# PicoInterface.net
KiCad netlist of a schematic drawn in Altium Designer
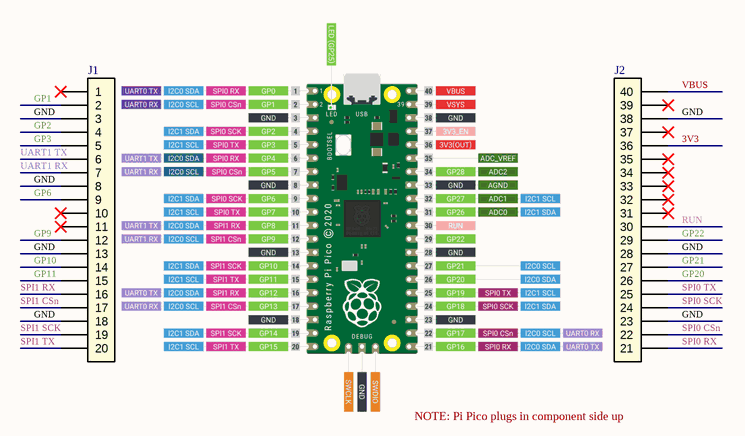
[diagram p0: PicoInterface.SchDoc]

(export (version "E")
  (design (tool "Eeschema 10.0.6"))
  (components
    (comp (ref "J1")
      (value "SSW-120-01-x-S")
      (footprint "SAMTEC_SSW-120-01-G-S")
      (description "Conn Socket Strip SKT 20 POS 2.54mm Solder ST Thru-Hole")
      (libsource (lib "Sainsbury Wellcome Centre") (part "Jack 20x1"))
    )
    (comp (ref "J2")
      (value "SSW-120-01-x-S - 21-40")
      (footprint "SAMTEC_SSW-120-01-G-S - 21-40")
      (description "Conn Socket Strip SKT 20 POS 2.54mm Solder ST Thru-Hole (pins 21 - 40)")
      (libsource (lib "Sainsbury Wellcome Centre") (part "Jack 20x1 21-40"))
    )
  )
  (nets
    (net (code "1") (name "/3V3") (class "Default")
      (node (ref "J2") (pin "36") (pinfunction "36_36") (pintype "passive"))
    )
    (net (code "2") (name "/GND") (class "Default")
      (node (ref "J1") (pin "13") (pinfunction "13_13") (pintype "passive"))
      (node (ref "J1") (pin "18") (pinfunction "18_18") (pintype "passive"))
      (node (ref "J1") (pin "3") (pinfunction "3_3") (pintype "passive"))
      (node (ref "J1") (pin "8") (pinfunction "8_8") (pintype "passive"))
      (node (ref "J2") (pin "23") (pinfunction "23_23") (pintype "passive"))
      (node (ref "J2") (pin "28") (pinfunction "28_28") (pintype "passive"))
      (node (ref "J2") (pin "38") (pinfunction "38_38") (pintype "passive"))
    )
    (net (code "3") (name "/GP1") (class "Default")
      (node (ref "J1") (pin "2") (pinfunction "2_2") (pintype "passive"))
    )
    (net (code "4") (name "/GP2") (class "Default")
      (node (ref "J1") (pin "4") (pinfunction "4_4") (pintype "passive"))
    )
    (net (code "5") (name "/GP3") (class "Default")
      (node (ref "J1") (pin "5") (pinfunction "5_5") (pintype "passive"))
    )
    (net (code "6") (name "/GP6") (class "Default")
      (node (ref "J1") (pin "9") (pinfunction "9_9") (pintype "passive"))
    )
    (net (code "7") (name "/GP9") (class "Default")
      (node (ref "J1") (pin "12") (pinfunction "12_12") (pintype "passive"))
    )
    (net (code "8") (name "/GP10") (class "Default")
      (node (ref "J1") (pin "14") (pinfunction "14_14") (pintype "passive"))
    )
    (net (code "9") (name "/GP11") (class "Default")
      (node (ref "J1") (pin "15") (pinfunction "15_15") (pintype "passive"))
    )
    (net (code "10") (name "/GP20") (class "Default")
      (node (ref "J2") (pin "26") (pinfunction "26_26") (pintype "passive"))
    )
    (net (code "11") (name "/GP21") (class "Default")
      (node (ref "J2") (pin "27") (pinfunction "27_27") (pintype "passive"))
    )
    (net (code "12") (name "/GP22") (class "Default")
      (node (ref "J2") (pin "29") (pinfunction "29_29") (pintype "passive"))
    )
    (net (code "13") (name "/RUN") (class "Default")
      (node (ref "J2") (pin "30") (pinfunction "30_30") (pintype "passive"))
    )
    (net (code "14") (name "/SPI0 CSn") (class "Default")
      (node (ref "J2") (pin "22") (pinfunction "22_22") (pintype "passive"))
    )
    (net (code "15") (name "/SPI0 RX") (class "Default")
      (node (ref "J2") (pin "21") (pinfunction "21_21") (pintype "passive"))
    )
    (net (code "16") (name "/SPI0 SCK") (class "Default")
      (node (ref "J2") (pin "24") (pinfunction "24_24") (pintype "passive"))
    )
    (net (code "17") (name "/SPI0 TX") (class "Default")
      (node (ref "J2") (pin "25") (pinfunction "25_25") (pintype "passive"))
    )
    (net (code "18") (name "/SPI1 CSn") (class "Default")
      (node (ref "J1") (pin "17") (pinfunction "17_17") (pintype "passive"))
    )
    (net (code "19") (name "/SPI1 RX") (class "Default")
      (node (ref "J1") (pin "16") (pinfunction "16_16") (pintype "passive"))
    )
    (net (code "20") (name "/SPI1 SCK") (class "Default")
      (node (ref "J1") (pin "19") (pinfunction "19_19") (pintype "passive"))
    )
    (net (code "21") (name "/SPI1 TX") (class "Default")
      (node (ref "J1") (pin "20") (pinfunction "20_20") (pintype "passive"))
    )
    (net (code "22") (name "/UART1 RX") (class "Default")
      (node (ref "J1") (pin "7") (pinfunction "7_7") (pintype "passive"))
    )
    (net (code "23") (name "/UART1 TX") (class "Default")
      (node (ref "J1") (pin "6") (pinfunction "6_6") (pintype "passive"))
    )
    (net (code "24") (name "/VBUS") (class "Default")
      (node (ref "J2") (pin "40") (pinfunction "40_40") (pintype "passive"))
    )
    (net (code "25") (name "unconnected-(J1-Pad1)") (class "Default")
      (node (ref "J1") (pin "1") (pinfunction "1_1") (pintype "passive+no_connect"))
    )
    (net (code "26") (name "unconnected-(J1-Pad10)") (class "Default")
      (node (ref "J1") (pin "10") (pinfunction "10_10") (pintype "passive+no_connect"))
    )
    (net (code "27") (name "unconnected-(J1-Pad11)") (class "Default")
      (node (ref "J1") (pin "11") (pinfunction "11_11") (pintype "passive+no_connect"))
    )
    (net (code "28") (name "unconnected-(J2-Pad31)") (class "Default")
      (node (ref "J2") (pin "31") (pinfunction "31_31") (pintype "passive+no_connect"))
    )
    (net (code "29") (name "unconnected-(J2-Pad32)") (class "Default")
      (node (ref "J2") (pin "32") (pinfunction "32_32") (pintype "passive+no_connect"))
    )
    (net (code "30") (name "unconnected-(J2-Pad33)") (class "Default")
      (node (ref "J2") (pin "33") (pinfunction "33_33") (pintype "passive+no_connect"))
    )
    (net (code "31") (name "unconnected-(J2-Pad34)") (class "Default")
      (node (ref "J2") (pin "34") (pinfunction "34_34") (pintype "passive+no_connect"))
    )
    (net (code "32") (name "unconnected-(J2-Pad35)") (class "Default")
      (node (ref "J2") (pin "35") (pinfunction "35_35") (pintype "passive+no_connect"))
    )
    (net (code "33") (name "unconnected-(J2-Pad37)") (class "Default")
      (node (ref "J2") (pin "37") (pinfunction "37_37") (pintype "passive+no_connect"))
    )
    (net (code "34") (name "unconnected-(J2-Pad39)") (class "Default")
      (node (ref "J2") (pin "39") (pinfunction "39_39") (pintype "passive+no_connect"))
    )
  )
)
